# PMIC.net
KiCad netlist of a schematic drawn in Altium Designer
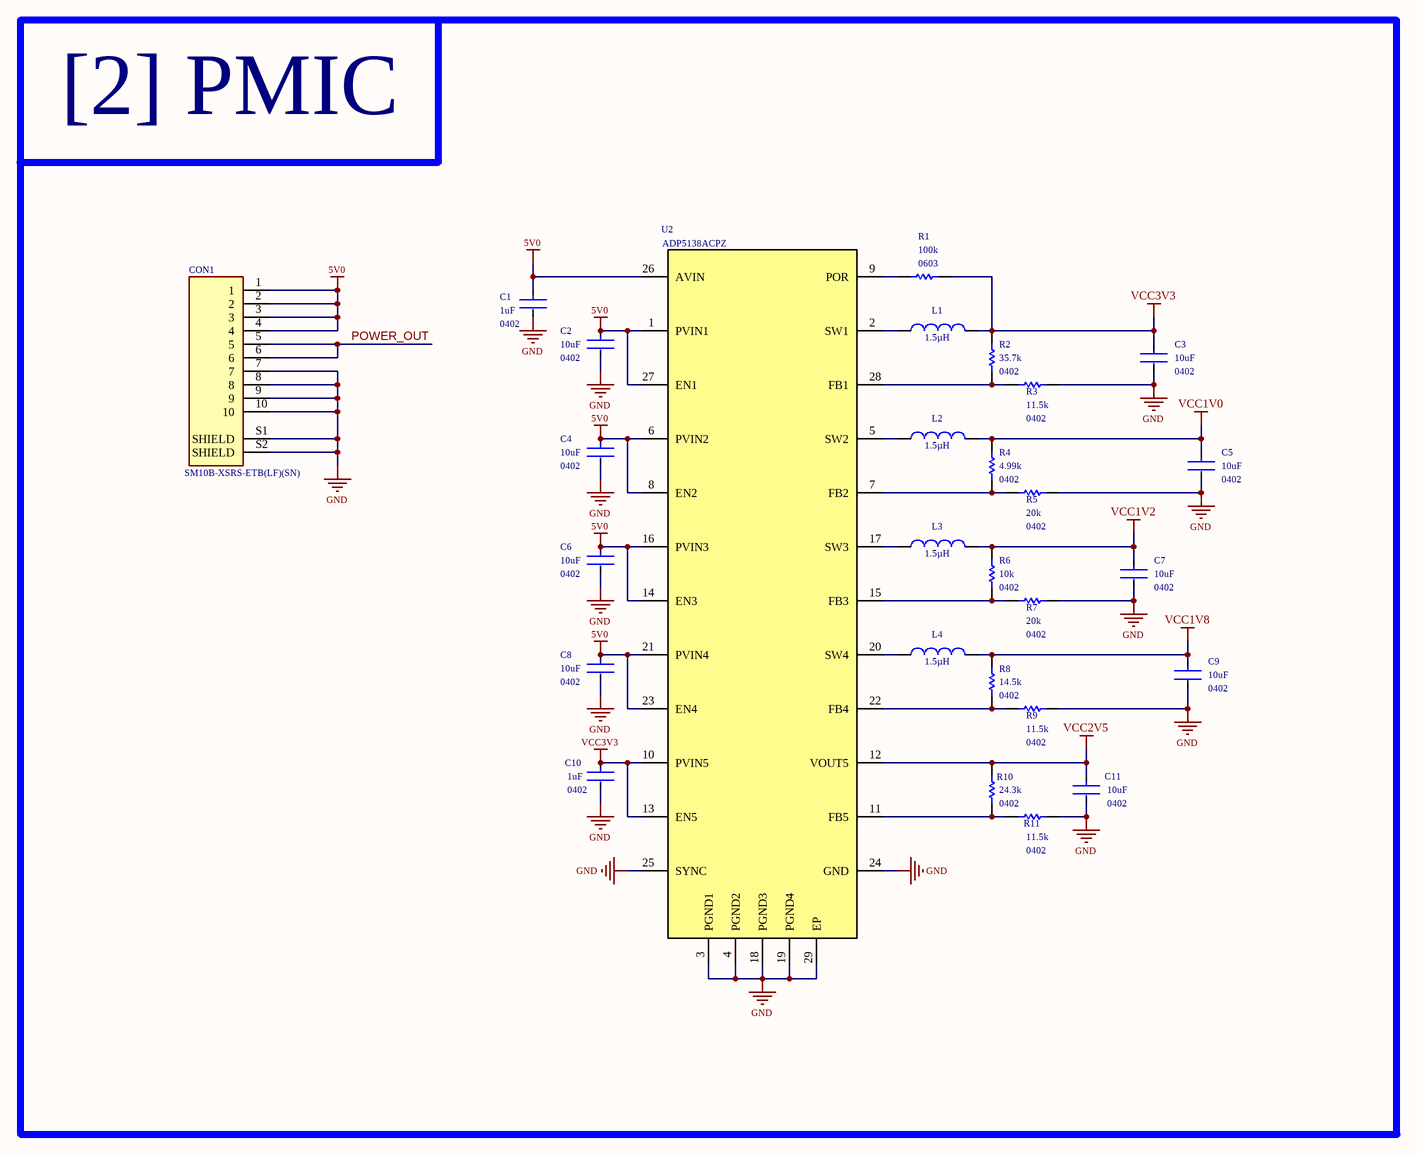
[diagram p0: PMIC.SchDoc]

(export (version "E")
  (design (tool "Eeschema 10.0.6"))
  (components
    (comp (ref "C1")
      (value "EMK105BJ105KV-F")
      (footprint "PCB_Display_Doru:FP-0402-L_1_0_0_05-W_0_5-IPC_A")
      (description "None")
      (fields
        (field (name "TOLERANCE") "10%")
        (field (name "CASE/PACKAGE") "0402")
        (field (name "CAPACITANCE") "1uF")
      )
      (libsource (lib "Camera_PCB_proj") (part "b4654b650e69147ec39a6b967a45e02"))
    )
    (comp (ref "C2")
      (value "GRM155R60J106ME44D")
      (footprint "PCB_Display_Doru:FP-GRM155-0_2-IPC_B")
      (description "CAP CER 10UF 6.3V X5R 0402")
      (fields
        (field (name "VOLTAGE") "6.3V")
        (field (name "TOLERANCE") "20%")
        (field (name "CASE/PACKAGE") "0402")
        (field (name "CAPACITANCE") "10uF")
      )
      (libsource (lib "Camera_PCB_proj") (part "b4654b650e69147ec39a6b967a45e02"))
    )
    (comp (ref "C3")
      (value "GRM155R60J106ME44D")
      (footprint "PCB_Display_Doru:FP-GRM155-0_2-IPC_B")
      (description "CAP CER 10UF 6.3V X5R 0402")
      (fields
        (field (name "VOLTAGE") "6.3V")
        (field (name "TOLERANCE") "20%")
        (field (name "CASE/PACKAGE") "0402")
        (field (name "CAPACITANCE") "10uF")
      )
      (libsource (lib "Camera_PCB_proj") (part "b4654b650e69147ec39a6b967a45e02"))
    )
    (comp (ref "C4")
      (value "GRM155R60J106ME44D")
      (footprint "PCB_Display_Doru:FP-GRM155-0_2-IPC_B")
      (description "CAP CER 10UF 6.3V X5R 0402")
      (fields
        (field (name "VOLTAGE") "6.3V")
        (field (name "TOLERANCE") "20%")
        (field (name "CASE/PACKAGE") "0402")
        (field (name "CAPACITANCE") "10uF")
      )
      (libsource (lib "Camera_PCB_proj") (part "b4654b650e69147ec39a6b967a45e02"))
    )
    (comp (ref "C5")
      (value "GRM155R60J106ME44D")
      (footprint "PCB_Display_Doru:FP-GRM155-0_2-IPC_B")
      (description "CAP CER 10UF 6.3V X5R 0402")
      (fields
        (field (name "VOLTAGE") "6.3V")
        (field (name "TOLERANCE") "20%")
        (field (name "CASE/PACKAGE") "0402")
        (field (name "CAPACITANCE") "10uF")
      )
      (libsource (lib "Camera_PCB_proj") (part "b4654b650e69147ec39a6b967a45e02"))
    )
    (comp (ref "C6")
      (value "GRM155R60J106ME44D")
      (footprint "PCB_Display_Doru:FP-GRM155-0_2-IPC_B")
      (description "CAP CER 10UF 6.3V X5R 0402")
      (fields
        (field (name "VOLTAGE") "6.3V")
        (field (name "TOLERANCE") "20%")
        (field (name "CASE/PACKAGE") "0402")
        (field (name "CAPACITANCE") "10uF")
      )
      (libsource (lib "Camera_PCB_proj") (part "b4654b650e69147ec39a6b967a45e02"))
    )
    (comp (ref "C7")
      (value "GRM155R60J106ME44D")
      (footprint "PCB_Display_Doru:FP-GRM155-0_2-IPC_B")
      (description "CAP CER 10UF 6.3V X5R 0402")
      (fields
        (field (name "VOLTAGE") "6.3V")
        (field (name "TOLERANCE") "20%")
        (field (name "CASE/PACKAGE") "0402")
        (field (name "CAPACITANCE") "10uF")
      )
      (libsource (lib "Camera_PCB_proj") (part "b4654b650e69147ec39a6b967a45e02"))
    )
    (comp (ref "C8")
      (value "GRM155R60J106ME44D")
      (footprint "PCB_Display_Doru:FP-GRM155-0_2-IPC_B")
      (description "CAP CER 10UF 6.3V X5R 0402")
      (fields
        (field (name "VOLTAGE") "6.3V")
        (field (name "TOLERANCE") "20%")
        (field (name "CASE/PACKAGE") "0402")
        (field (name "CAPACITANCE") "10uF")
      )
      (libsource (lib "Camera_PCB_proj") (part "b4654b650e69147ec39a6b967a45e02"))
    )
    (comp (ref "C9")
      (value "GRM155R60J106ME44D")
      (footprint "PCB_Display_Doru:FP-GRM155-0_2-IPC_B")
      (description "CAP CER 10UF 6.3V X5R 0402")
      (fields
        (field (name "VOLTAGE") "6.3V")
        (field (name "TOLERANCE") "20%")
        (field (name "CASE/PACKAGE") "0402")
        (field (name "CAPACITANCE") "10uF")
      )
      (libsource (lib "Camera_PCB_proj") (part "b4654b650e69147ec39a6b967a45e02"))
    )
    (comp (ref "C10")
      (value "EMK105BJ105KV-F")
      (footprint "PCB_Display_Doru:FP-0402-L_1_0_0_05-W_0_5-IPC_A")
      (description "None")
      (fields
        (field (name "TOLERANCE") "10%")
        (field (name "CASE/PACKAGE") "0402")
        (field (name "CAPACITANCE") "1uF")
      )
      (libsource (lib "Camera_PCB_proj") (part "b4654b650e69147ec39a6b967a45e02"))
    )
    (comp (ref "C11")
      (value "GRM155R60J106ME44D")
      (footprint "PCB_Display_Doru:FP-GRM155-0_2-IPC_B")
      (description "CAP CER 10UF 6.3V X5R 0402")
      (fields
        (field (name "VOLTAGE") "6.3V")
        (field (name "TOLERANCE") "20%")
        (field (name "CASE/PACKAGE") "0402")
        (field (name "CAPACITANCE") "10uF")
      )
      (libsource (lib "Camera_PCB_proj") (part "b4654b650e69147ec39a6b967a45e02"))
    )
    (comp (ref "CON1")
      (value "SM10B-XSRS-ETB(LF)(SN)")
      (footprint "PCB_Display_Doru:SM10B-XSRS-ETB")
      (fields (field (name "PART_NUMBER") "J00001"))
      (libsource (lib "PCB_Display_Doru") (part "SM10B-XSRS-ETB(LF)(SN)"))
    )
    (comp (ref "L1")
      (value "744031001")
      (footprint "PCB_Display_Doru:WE-TPC-3816-S")
      (description "SMD Shielded Tiny Power Inductor WE-TPC, L = 1.50 µH")
      (fields (field (name "INDUCTANCE") "1.5µH"))
      (libsource (lib "Camera_PCB_proj") (part "PAS-IND-INDUCTOR-2"))
    )
    (comp (ref "L2")
      (value "744031001")
      (footprint "PCB_Display_Doru:WE-TPC-3816-S")
      (description "SMD Shielded Tiny Power Inductor WE-TPC, L = 1.50 µH")
      (fields (field (name "INDUCTANCE") "1.5µH"))
      (libsource (lib "Camera_PCB_proj") (part "PAS-IND-INDUCTOR-2"))
    )
    (comp (ref "L3")
      (value "744031001")
      (footprint "PCB_Display_Doru:WE-TPC-3816-S")
      (description "SMD Shielded Tiny Power Inductor WE-TPC, L = 1.50 µH")
      (fields (field (name "INDUCTANCE") "1.5µH"))
      (libsource (lib "Camera_PCB_proj") (part "PAS-IND-INDUCTOR-2"))
    )
    (comp (ref "L4")
      (value "744031001")
      (footprint "PCB_Display_Doru:WE-TPC-3816-S")
      (description "SMD Shielded Tiny Power Inductor WE-TPC, L = 1.50 µH")
      (fields (field (name "INDUCTANCE") "1.5µH"))
      (libsource (lib "Camera_PCB_proj") (part "PAS-IND-INDUCTOR-2"))
    )
    (comp (ref "R1")
      (value "100k")
      (footprint "PCB_Display_Doru:RESC1608X55X30ML20T20")
      (fields
        (field (name "PART NUMBER") "ERA3AEB104V")
        (field (name "MANUFACTURER") "Panasonic")
        (field (name "PACKAGE") "0603")
      )
      (libsource (lib "Camera_PCB_proj") (part "RES"))
    )
    (comp (ref "R2")
      (value "RC0402FR-0735K7L")
      (footprint "PCB_Display_Doru:RESC1005X40X25NL05T10")
      (fields
        (field (name "MANUFACTURER") "Yageo / Phycomp")
        (field (name "PARAMETER 1") "35.7k")
        (field (name "PARAMETER 2") "0402")
      )
      (libsource (lib "Camera_PCB_proj") (part "RES"))
    )
    (comp (ref "R3")
      (value "RC0402FR-0711K5L")
      (footprint "PCB_Display_Doru:RESC1005X40X25NL05T10")
      (fields
        (field (name "MANUFACTURER") "Yageo / Phycomp")
        (field (name "PARAMETER 3") "11.5k")
        (field (name "PARAMETER 4") "0402")
      )
      (libsource (lib "Camera_PCB_proj") (part "RES"))
    )
    (comp (ref "R4")
      (value "RC0402FR-074K99L")
      (footprint "PCB_Display_Doru:RESC1005X40X25NL05T10")
      (fields
        (field (name "MANUFACTURER") "Yageo / Phycomp")
        (field (name "PARAMETER 3") "4.99k")
        (field (name "PARAMETER 4") "0402")
      )
      (libsource (lib "Camera_PCB_proj") (part "RES"))
    )
    (comp (ref "R5")
      (value "RC0402FR-0720KL")
      (footprint "PCB_Display_Doru:RESC1005X40X25NL05T10")
      (fields
        (field (name "MANUFACTURER") "Yageo / Phycomp")
        (field (name "PARAMETER 3") "20k")
        (field (name "PARAMETER 4") "0402")
      )
      (libsource (lib "Camera_PCB_proj") (part "RES"))
    )
    (comp (ref "R6")
      (value "RC0402FR-0710KL")
      (footprint "PCB_Display_Doru:RESC1005X40X25NL05T10")
      (fields
        (field (name "MANUFACTURER") "Yageo / Phycomp")
        (field (name "PARAMETER 3") "10k")
        (field (name "PARAMETER 4") "0402")
      )
      (libsource (lib "Camera_PCB_proj") (part "RES"))
    )
    (comp (ref "R7")
      (value "RC0402FR-0720KL")
      (footprint "PCB_Display_Doru:RESC1005X40X25NL05T10")
      (fields
        (field (name "MANUFACTURER") "Yageo / Phycomp")
        (field (name "PARAMETER 3") "20k")
        (field (name "PARAMETER 4") "0402")
      )
      (libsource (lib "Camera_PCB_proj") (part "RES"))
    )
    (comp (ref "R8")
      (value "RN73H1ETTP1452F25")
      (footprint "PCB_Display_Doru:RESC1005X40N")
      (fields (field (name "PARAMETER 3") "14.5k") (field (name "PARAMETER 4") "0402"))
      (libsource (lib "Camera_PCB_proj") (part "RN73H1ETTP1452F25"))
    )
    (comp (ref "R9")
      (value "RC0402FR-0711K5L")
      (footprint "PCB_Display_Doru:RESC1005X40X25NL05T10")
      (fields
        (field (name "MANUFACTURER") "Yageo / Phycomp")
        (field (name "PARAMETER 3") "11.5k")
        (field (name "PARAMETER 4") "0402")
      )
      (libsource (lib "Camera_PCB_proj") (part "RES"))
    )
    (comp (ref "R10")
      (value "RC0402FR-0724K3L")
      (footprint "PCB_Display_Doru:RESC1005X40X25NL05T10")
      (fields
        (field (name "MANUFACTURER") "Yageo")
        (field (name "PARAMETER 3") "24.3k")
        (field (name "PARAMETER 4") "0402")
      )
      (libsource (lib "Camera_PCB_proj") (part "RES"))
    )
    (comp (ref "R11")
      (value "RC0402FR-0711K5L")
      (footprint "PCB_Display_Doru:RESC1005X40X25NL05T10")
      (fields
        (field (name "MANUFACTURER") "Yageo / Phycomp")
        (field (name "PARAMETER 3") "11.5k")
        (field (name "PARAMETER 4") "0402")
      )
      (libsource (lib "Camera_PCB_proj") (part "RES"))
    )
    (comp (ref "U2")
      (value "ADP5138ACPZ")
      (footprint "PCB_Display_Doru:CP_28_5")
      (description "No Description Available")
      (fields (field (name "COPYRIGHT") "Copyright (C) 2021 Accelerated Designs. All rights reserved"))
      (libsource (lib "Camera_PCB_proj") (part "ADP5138ACPZ"))
    )
  )
  (nets
    (net (code "1") (name "/POWER_OUT") (class "Default")
      (node (ref "CON1") (pin "5") (pinfunction "5_5") (pintype "passive"))
      (node (ref "CON1") (pin "6") (pinfunction "6_6") (pintype "passive"))
    )
    (net (code "2") (name "5V0") (class "Default")
      (node (ref "C1") (pin "1") (pinfunction "1_1") (pintype "passive"))
      (node (ref "C2") (pin "1") (pinfunction "1_1") (pintype "passive"))
      (node (ref "C4") (pin "1") (pinfunction "1_1") (pintype "passive"))
      (node (ref "C6") (pin "1") (pinfunction "1_1") (pintype "passive"))
      (node (ref "C8") (pin "1") (pinfunction "1_1") (pintype "passive"))
      (node (ref "CON1") (pin "1") (pinfunction "1_1") (pintype "passive"))
      (node (ref "CON1") (pin "2") (pinfunction "2_2") (pintype "passive"))
      (node (ref "CON1") (pin "3") (pinfunction "3_3") (pintype "passive"))
      (node (ref "CON1") (pin "4") (pinfunction "4_4") (pintype "passive"))
      (node (ref "U2") (pin "1") (pinfunction "PVIN1_1") (pintype "passive"))
      (node (ref "U2") (pin "14") (pinfunction "EN3_14") (pintype "passive"))
      (node (ref "U2") (pin "16") (pinfunction "PVIN3_16") (pintype "passive"))
      (node (ref "U2") (pin "21") (pinfunction "PVIN4_21") (pintype "passive"))
      (node (ref "U2") (pin "23") (pinfunction "EN4_23") (pintype "passive"))
      (node (ref "U2") (pin "26") (pinfunction "AVIN_26") (pintype "passive"))
      (node (ref "U2") (pin "27") (pinfunction "EN1_27") (pintype "passive"))
      (node (ref "U2") (pin "6") (pinfunction "PVIN2_6") (pintype "passive"))
      (node (ref "U2") (pin "8") (pinfunction "EN2_8") (pintype "passive"))
    )
    (net (code "3") (name "GND") (class "Default")
      (node (ref "C1") (pin "2") (pinfunction "2_2") (pintype "passive"))
      (node (ref "C10") (pin "2") (pinfunction "2_2") (pintype "passive"))
      (node (ref "C11") (pin "2") (pinfunction "2_2") (pintype "passive"))
      (node (ref "C2") (pin "2") (pinfunction "2_2") (pintype "passive"))
      (node (ref "C3") (pin "2") (pinfunction "2_2") (pintype "passive"))
      (node (ref "C4") (pin "2") (pinfunction "2_2") (pintype "passive"))
      (node (ref "C5") (pin "2") (pinfunction "2_2") (pintype "passive"))
      (node (ref "C6") (pin "2") (pinfunction "2_2") (pintype "passive"))
      (node (ref "C7") (pin "2") (pinfunction "2_2") (pintype "passive"))
      (node (ref "C8") (pin "2") (pinfunction "2_2") (pintype "passive"))
      (node (ref "C9") (pin "2") (pinfunction "2_2") (pintype "passive"))
      (node (ref "CON1") (pin "10") (pinfunction "10_10") (pintype "passive"))
      (node (ref "CON1") (pin "7") (pinfunction "7_7") (pintype "passive"))
      (node (ref "CON1") (pin "8") (pinfunction "8_8") (pintype "passive"))
      (node (ref "CON1") (pin "9") (pinfunction "9_9") (pintype "passive"))
      (node (ref "CON1") (pin "S1") (pinfunction "SHIELD_S1") (pintype "passive"))
      (node (ref "CON1") (pin "S2") (pinfunction "SHIELD_S2") (pintype "passive"))
      (node (ref "R11") (pin "2") (pinfunction "2_2") (pintype "passive"))
      (node (ref "R3") (pin "2") (pinfunction "2_2") (pintype "passive"))
      (node (ref "R5") (pin "2") (pinfunction "2_2") (pintype "passive"))
      (node (ref "R7") (pin "2") (pinfunction "2_2") (pintype "passive"))
      (node (ref "R9") (pin "2") (pinfunction "2_2") (pintype "passive"))
      (node (ref "U2") (pin "18") (pinfunction "PGND3_18") (pintype "passive"))
      (node (ref "U2") (pin "19") (pinfunction "PGND4_19") (pintype "passive"))
      (node (ref "U2") (pin "24") (pinfunction "GND_24") (pintype "passive"))
      (node (ref "U2") (pin "25") (pinfunction "SYNC_25") (pintype "passive"))
      (node (ref "U2") (pin "29") (pinfunction "EP_29") (pintype "passive"))
      (node (ref "U2") (pin "3") (pinfunction "PGND1_3") (pintype "passive"))
      (node (ref "U2") (pin "4") (pinfunction "PGND2_4") (pintype "passive"))
    )
    (net (code "4") (name "Net-(U2-FB1)") (class "Default")
      (node (ref "R2") (pin "1") (pinfunction "1_1") (pintype "passive"))
      (node (ref "R3") (pin "1") (pinfunction "1_1") (pintype "passive"))
      (node (ref "U2") (pin "28") (pinfunction "FB1_28") (pintype "passive"))
    )
    (net (code "5") (name "Net-(U2-FB2)") (class "Default")
      (node (ref "R4") (pin "1") (pinfunction "1_1") (pintype "passive"))
      (node (ref "R5") (pin "1") (pinfunction "1_1") (pintype "passive"))
      (node (ref "U2") (pin "7") (pinfunction "FB2_7") (pintype "passive"))
    )
    (net (code "6") (name "Net-(U2-FB3)") (class "Default")
      (node (ref "R6") (pin "1") (pinfunction "1_1") (pintype "passive"))
      (node (ref "R7") (pin "1") (pinfunction "1_1") (pintype "passive"))
      (node (ref "U2") (pin "15") (pinfunction "FB3_15") (pintype "passive"))
    )
    (net (code "7") (name "Net-(U2-FB4)") (class "Default")
      (node (ref "R8") (pin "1") (pinfunction "1_1") (pintype "passive"))
      (node (ref "R9") (pin "1") (pinfunction "1_1") (pintype "passive"))
      (node (ref "U2") (pin "22") (pinfunction "FB4_22") (pintype "passive"))
    )
    (net (code "8") (name "Net-(U2-FB5)") (class "Default")
      (node (ref "R10") (pin "1") (pinfunction "1_1") (pintype "passive"))
      (node (ref "R11") (pin "1") (pinfunction "1_1") (pintype "passive"))
      (node (ref "U2") (pin "11") (pinfunction "FB5_11") (pintype "passive"))
    )
    (net (code "9") (name "Net-(U2-POR)") (class "Default")
      (node (ref "R1") (pin "1") (pinfunction "1_1") (pintype "passive"))
      (node (ref "U2") (pin "9") (pinfunction "POR_9") (pintype "passive"))
    )
    (net (code "10") (name "Net-(U2-SW1)") (class "Default")
      (node (ref "L1") (pin "1") (pinfunction "1_1") (pintype "passive"))
      (node (ref "U2") (pin "2") (pinfunction "SW1_2") (pintype "passive"))
    )
    (net (code "11") (name "Net-(U2-SW2)") (class "Default")
      (node (ref "L2") (pin "1") (pinfunction "1_1") (pintype "passive"))
      (node (ref "U2") (pin "5") (pinfunction "SW2_5") (pintype "passive"))
    )
    (net (code "12") (name "Net-(U2-SW3)") (class "Default")
      (node (ref "L3") (pin "1") (pinfunction "1_1") (pintype "passive"))
      (node (ref "U2") (pin "17") (pinfunction "SW3_17") (pintype "passive"))
    )
    (net (code "13") (name "Net-(U2-SW4)") (class "Default")
      (node (ref "L4") (pin "1") (pinfunction "1_1") (pintype "passive"))
      (node (ref "U2") (pin "20") (pinfunction "SW4_20") (pintype "passive"))
    )
    (net (code "14") (name "VCC1V0") (class "Default")
      (node (ref "C5") (pin "1") (pinfunction "1_1") (pintype "passive"))
      (node (ref "L2") (pin "2") (pinfunction "2_2") (pintype "passive"))
      (node (ref "R4") (pin "2") (pinfunction "2_2") (pintype "passive"))
    )
    (net (code "15") (name "VCC1V2") (class "Default")
      (node (ref "C7") (pin "1") (pinfunction "1_1") (pintype "passive"))
      (node (ref "L3") (pin "2") (pinfunction "2_2") (pintype "passive"))
      (node (ref "R6") (pin "2") (pinfunction "2_2") (pintype "passive"))
    )
    (net (code "16") (name "VCC1V8") (class "Default")
      (node (ref "C9") (pin "1") (pinfunction "1_1") (pintype "passive"))
      (node (ref "L4") (pin "2") (pinfunction "2_2") (pintype "passive"))
      (node (ref "R8") (pin "2") (pinfunction "2_2") (pintype "passive"))
    )
    (net (code "17") (name "VCC2V5") (class "Default")
      (node (ref "C11") (pin "1") (pinfunction "1_1") (pintype "passive"))
      (node (ref "R10") (pin "2") (pinfunction "2_2") (pintype "passive"))
      (node (ref "U2") (pin "12") (pinfunction "VOUT5_12") (pintype "passive"))
    )
    (net (code "18") (name "VCC3V3") (class "Default")
      (node (ref "C10") (pin "1") (pinfunction "1_1") (pintype "passive"))
      (node (ref "C3") (pin "1") (pinfunction "1_1") (pintype "passive"))
      (node (ref "L1") (pin "2") (pinfunction "2_2") (pintype "passive"))
      (node (ref "R1") (pin "2") (pinfunction "2_2") (pintype "passive"))
      (node (ref "R2") (pin "2") (pinfunction "2_2") (pintype "passive"))
      (node (ref "U2") (pin "10") (pinfunction "PVIN5_10") (pintype "passive"))
      (node (ref "U2") (pin "13") (pinfunction "EN5_13") (pintype "passive"))
    )
  )
)
